# RCDudelTiny.net
KiCad netlist of a schematic drawn in EAGLE
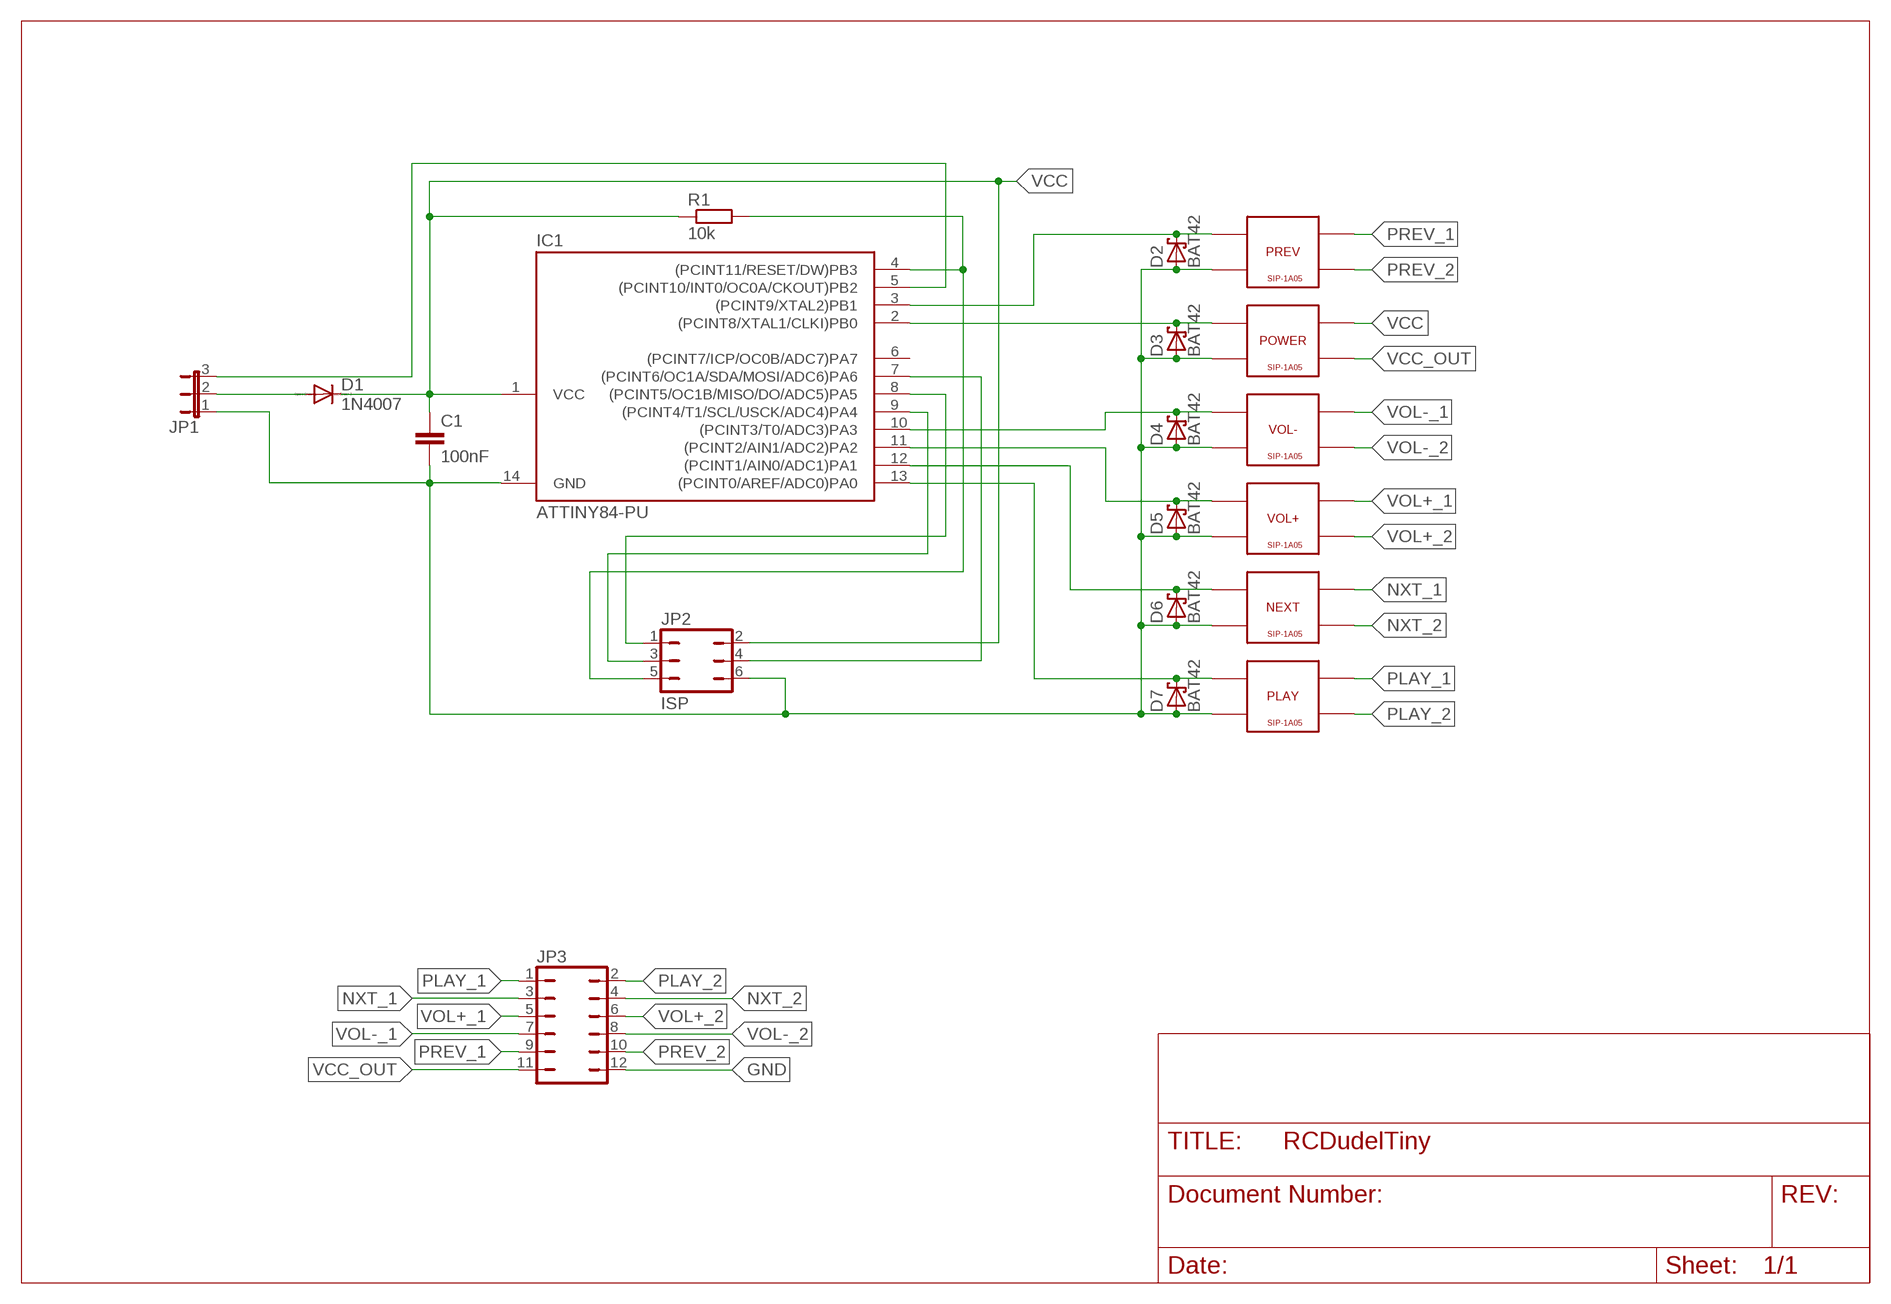
[diagram p0: schematic, sheet 1]

(export (version "E")
  (design (tool "Eeschema 10.0.6"))
  (components
    (comp (ref "C1")
      (value "100nF")
      (footprint "eagle-import:C025-025X050")
      (libsource (lib "eagle-import") (part "C-EU025-025X050"))
    )
    (comp (ref "D1")
      (value "1N4007")
      (footprint "eagle-import:DO41-10")
      (libsource (lib "eagle-import") (part "1N4004"))
    )
    (comp (ref "D2")
      (value "BAT42")
      (footprint "eagle-import:DO35-10")
      (libsource (lib "eagle-import") (part "BAT42"))
    )
    (comp (ref "D3")
      (value "BAT42")
      (footprint "eagle-import:DO35-10")
      (libsource (lib "eagle-import") (part "BAT42"))
    )
    (comp (ref "D4")
      (value "BAT42")
      (footprint "eagle-import:DO35-10")
      (libsource (lib "eagle-import") (part "BAT42"))
    )
    (comp (ref "D5")
      (value "BAT42")
      (footprint "eagle-import:DO35-10")
      (libsource (lib "eagle-import") (part "BAT42"))
    )
    (comp (ref "D6")
      (value "BAT42")
      (footprint "eagle-import:DO35-10")
      (libsource (lib "eagle-import") (part "BAT42"))
    )
    (comp (ref "D7")
      (value "BAT42")
      (footprint "eagle-import:DO35-10")
      (libsource (lib "eagle-import") (part "BAT42"))
    )
    (comp (ref "IC1")
      (value "ATTINY84-PU")
      (footprint "eagle-import:DIL14")
      (libsource (lib "eagle-import") (part "TINY24/44/84-PU"))
    )
    (comp (ref "JP1")
      (value "JP2EJP2_OHNE_TEXT")
      (footprint "eagle-import:JP2")
      (libsource (lib "eagle-import") (part "JP2EJP2_OHNE_TEXT"))
    )
    (comp (ref "JP2")
      (value "ISP")
      (footprint "eagle-import:JP3Q")
      (libsource (lib "eagle-import") (part "JP3Q"))
    )
    (comp (ref "JP3")
      (value "JP6Q")
      (footprint "eagle-import:JP6Q")
      (libsource (lib "eagle-import") (part "JP6Q"))
    )
    (comp (ref "NEXT")
      (value "SIP1A05")
      (footprint "eagle-import:SIP1A05")
      (libsource (lib "eagle-import") (part "SIP1A05"))
    )
    (comp (ref "PLAY")
      (value "SIP1A05")
      (footprint "eagle-import:SIP1A05")
      (libsource (lib "eagle-import") (part "SIP1A05"))
    )
    (comp (ref "POWER")
      (value "SIP1A05")
      (footprint "eagle-import:SIP1A05")
      (libsource (lib "eagle-import") (part "SIP1A05"))
    )
    (comp (ref "PREV")
      (value "SIP1A05")
      (footprint "eagle-import:SIP1A05")
      (libsource (lib "eagle-import") (part "SIP1A05"))
    )
    (comp (ref "R1")
      (value "10k")
      (footprint "eagle-import:0207_7")
      (libsource (lib "eagle-import") (part "R-EU_0207/7"))
    )
    (comp (ref "VOL+")
      (value "SIP1A05")
      (footprint "eagle-import:SIP1A05")
      (libsource (lib "eagle-import") (part "SIP1A05"))
    )
    (comp (ref "VOL-")
      (value "SIP1A05")
      (footprint "eagle-import:SIP1A05")
      (libsource (lib "eagle-import") (part "SIP1A05"))
    )
  )
  (nets
    (net (code "1") (name "GND") (class "Default")
      (node (ref "C1") (pin "2") (pinfunction "2_2") (pintype "passive"))
      (node (ref "D2") (pin "A") (pinfunction "A_A") (pintype "passive"))
      (node (ref "D3") (pin "A") (pinfunction "A_A") (pintype "passive"))
      (node (ref "D4") (pin "A") (pinfunction "A_A") (pintype "passive"))
      (node (ref "D5") (pin "A") (pinfunction "A_A") (pintype "passive"))
      (node (ref "D6") (pin "A") (pinfunction "A_A") (pintype "passive"))
      (node (ref "D7") (pin "A") (pinfunction "A_A") (pintype "passive"))
      (node (ref "IC1") (pin "14") (pinfunction "GND_14") (pintype "power_in"))
      (node (ref "JP1") (pin "1") (pinfunction "1_1") (pintype "passive"))
      (node (ref "JP2") (pin "6") (pinfunction "6_6") (pintype "passive"))
      (node (ref "JP3") (pin "12") (pinfunction "12_12") (pintype "passive"))
      (node (ref "NEXT") (pin "SP2") (pinfunction "SP2_SP2") (pintype "bidirectional"))
      (node (ref "PLAY") (pin "SP2") (pinfunction "SP2_SP2") (pintype "bidirectional"))
      (node (ref "POWER") (pin "SP2") (pinfunction "SP2_SP2") (pintype "bidirectional"))
      (node (ref "PREV") (pin "SP2") (pinfunction "SP2_SP2") (pintype "bidirectional"))
      (node (ref "VOL+") (pin "SP2") (pinfunction "SP2_SP2") (pintype "bidirectional"))
      (node (ref "VOL-") (pin "SP2") (pinfunction "SP2_SP2") (pintype "bidirectional"))
    )
    (net (code "2") (name "NXT_1") (class "Default")
      (node (ref "JP3") (pin "3") (pinfunction "3_3") (pintype "passive"))
      (node (ref "NEXT") (pin "K1") (pinfunction "K1_K1") (pintype "bidirectional"))
    )
    (net (code "3") (name "NXT_2") (class "Default")
      (node (ref "JP3") (pin "4") (pinfunction "4_4") (pintype "passive"))
      (node (ref "NEXT") (pin "K2") (pinfunction "K2_K2") (pintype "bidirectional"))
    )
    (net (code "4") (name "Net-(D1-PadA)") (class "Default")
      (node (ref "D1") (pin "A") (pinfunction "A_A") (pintype "passive"))
      (node (ref "JP1") (pin "2") (pinfunction "2_2") (pintype "passive"))
    )
    (net (code "5") (name "Net-(IC1-(PCINT0{slash}AREF{slash}ADC0)PA0)") (class "Default")
      (node (ref "D7") (pin "C") (pinfunction "C_C") (pintype "passive"))
      (node (ref "IC1") (pin "13") (pinfunction "(PCINT0/AREF/ADC0)PA0_13") (pintype "bidirectional"))
      (node (ref "PLAY") (pin "SP1") (pinfunction "SP1_SP1") (pintype "bidirectional"))
    )
    (net (code "6") (name "Net-(IC1-(PCINT1{slash}AIN0{slash}ADC1)PA1)") (class "Default")
      (node (ref "D6") (pin "C") (pinfunction "C_C") (pintype "passive"))
      (node (ref "IC1") (pin "12") (pinfunction "(PCINT1/AIN0/ADC1)PA1_12") (pintype "bidirectional"))
      (node (ref "NEXT") (pin "SP1") (pinfunction "SP1_SP1") (pintype "bidirectional"))
    )
    (net (code "7") (name "Net-(IC1-(PCINT2{slash}AIN1{slash}ADC2)PA2)") (class "Default")
      (node (ref "D5") (pin "C") (pinfunction "C_C") (pintype "passive"))
      (node (ref "IC1") (pin "11") (pinfunction "(PCINT2/AIN1/ADC2)PA2_11") (pintype "bidirectional"))
      (node (ref "VOL+") (pin "SP1") (pinfunction "SP1_SP1") (pintype "bidirectional"))
    )
    (net (code "8") (name "Net-(IC1-(PCINT3{slash}T0{slash}ADC3)PA3)") (class "Default")
      (node (ref "D4") (pin "C") (pinfunction "C_C") (pintype "passive"))
      (node (ref "IC1") (pin "10") (pinfunction "(PCINT3/T0/ADC3)PA3_10") (pintype "bidirectional"))
      (node (ref "VOL-") (pin "SP1") (pinfunction "SP1_SP1") (pintype "bidirectional"))
    )
    (net (code "9") (name "Net-(IC1-(PCINT4{slash}T1{slash}SCL{slash}USCK{slash}ADC4)PA4)") (class "Default")
      (node (ref "IC1") (pin "9") (pinfunction "(PCINT4/T1/SCL/USCK/ADC4)PA4_9") (pintype "bidirectional"))
      (node (ref "JP2") (pin "3") (pinfunction "3_3") (pintype "passive"))
    )
    (net (code "10") (name "Net-(IC1-(PCINT5{slash}OC1B{slash}MISO{slash}DO{slash}ADC5)PA5)") (class "Default")
      (node (ref "IC1") (pin "8") (pinfunction "(PCINT5/OC1B/MISO/DO/ADC5)PA5_8") (pintype "bidirectional"))
      (node (ref "JP2") (pin "1") (pinfunction "1_1") (pintype "passive"))
    )
    (net (code "11") (name "Net-(IC1-(PCINT6{slash}OC1A{slash}SDA{slash}MOSI{slash}ADC6)PA6)") (class "Default")
      (node (ref "IC1") (pin "7") (pinfunction "(PCINT6/OC1A/SDA/MOSI/ADC6)PA6_7") (pintype "bidirectional"))
      (node (ref "JP2") (pin "4") (pinfunction "4_4") (pintype "passive"))
    )
    (net (code "12") (name "Net-(IC1-(PCINT8{slash}XTAL1{slash}CLKI)PB0)") (class "Default")
      (node (ref "D3") (pin "C") (pinfunction "C_C") (pintype "passive"))
      (node (ref "IC1") (pin "2") (pinfunction "(PCINT8/XTAL1/CLKI)PB0_2") (pintype "bidirectional"))
      (node (ref "POWER") (pin "SP1") (pinfunction "SP1_SP1") (pintype "bidirectional"))
    )
    (net (code "13") (name "Net-(IC1-(PCINT9{slash}XTAL2)PB1)") (class "Default")
      (node (ref "D2") (pin "C") (pinfunction "C_C") (pintype "passive"))
      (node (ref "IC1") (pin "3") (pinfunction "(PCINT9/XTAL2)PB1_3") (pintype "bidirectional"))
      (node (ref "PREV") (pin "SP1") (pinfunction "SP1_SP1") (pintype "bidirectional"))
    )
    (net (code "14") (name "Net-(IC1-(PCINT10{slash}INT0{slash}OC0A{slash}CKOUT)PB2)") (class "Default")
      (node (ref "IC1") (pin "5") (pinfunction "(PCINT10/INT0/OC0A/CKOUT)PB2_5") (pintype "bidirectional"))
      (node (ref "JP1") (pin "3") (pinfunction "3_3") (pintype "passive"))
    )
    (net (code "15") (name "Net-(IC1-(PCINT11{slash}RESET{slash}DW)PB3)") (class "Default")
      (node (ref "IC1") (pin "4") (pinfunction "(PCINT11/RESET/DW)PB3_4") (pintype "bidirectional"))
      (node (ref "JP2") (pin "5") (pinfunction "5_5") (pintype "passive"))
      (node (ref "R1") (pin "2") (pinfunction "2_2") (pintype "passive"))
    )
    (net (code "16") (name "PLAY_1") (class "Default")
      (node (ref "JP3") (pin "1") (pinfunction "1_1") (pintype "passive"))
      (node (ref "PLAY") (pin "K1") (pinfunction "K1_K1") (pintype "bidirectional"))
    )
    (net (code "17") (name "PLAY_2") (class "Default")
      (node (ref "JP3") (pin "2") (pinfunction "2_2") (pintype "passive"))
      (node (ref "PLAY") (pin "K2") (pinfunction "K2_K2") (pintype "bidirectional"))
    )
    (net (code "18") (name "PREV_1") (class "Default")
      (node (ref "JP3") (pin "9") (pinfunction "9_9") (pintype "passive"))
      (node (ref "PREV") (pin "K1") (pinfunction "K1_K1") (pintype "bidirectional"))
    )
    (net (code "19") (name "PREV_2") (class "Default")
      (node (ref "JP3") (pin "10") (pinfunction "10_10") (pintype "passive"))
      (node (ref "PREV") (pin "K2") (pinfunction "K2_K2") (pintype "bidirectional"))
    )
    (net (code "20") (name "VCC") (class "Default")
      (node (ref "C1") (pin "1") (pinfunction "1_1") (pintype "passive"))
      (node (ref "D1") (pin "C") (pinfunction "C_C") (pintype "passive"))
      (node (ref "IC1") (pin "1") (pinfunction "VCC_1") (pintype "power_in"))
      (node (ref "JP2") (pin "2") (pinfunction "2_2") (pintype "passive"))
      (node (ref "POWER") (pin "K1") (pinfunction "K1_K1") (pintype "bidirectional"))
      (node (ref "R1") (pin "1") (pinfunction "1_1") (pintype "passive"))
    )
    (net (code "21") (name "VCC_OUT") (class "Default")
      (node (ref "JP3") (pin "11") (pinfunction "11_11") (pintype "passive"))
      (node (ref "POWER") (pin "K2") (pinfunction "K2_K2") (pintype "bidirectional"))
    )
    (net (code "22") (name "VOL+_1") (class "Default")
      (node (ref "JP3") (pin "5") (pinfunction "5_5") (pintype "passive"))
      (node (ref "VOL+") (pin "K1") (pinfunction "K1_K1") (pintype "bidirectional"))
    )
    (net (code "23") (name "VOL+_2") (class "Default")
      (node (ref "JP3") (pin "6") (pinfunction "6_6") (pintype "passive"))
      (node (ref "VOL+") (pin "K2") (pinfunction "K2_K2") (pintype "bidirectional"))
    )
    (net (code "24") (name "VOL-_1") (class "Default")
      (node (ref "JP3") (pin "7") (pinfunction "7_7") (pintype "passive"))
      (node (ref "VOL-") (pin "K1") (pinfunction "K1_K1") (pintype "bidirectional"))
    )
    (net (code "25") (name "VOL-_2") (class "Default")
      (node (ref "JP3") (pin "8") (pinfunction "8_8") (pintype "passive"))
      (node (ref "VOL-") (pin "K2") (pinfunction "K2_K2") (pintype "bidirectional"))
    )
    (net (code "26") (name "unconnected-(IC1-(PCINT7{slash}ICP{slash}OC0B{slash}ADC7)PA7-Pad6)") (class "Default")
      (node (ref "IC1") (pin "6") (pinfunction "(PCINT7/ICP/OC0B/ADC7)PA7_6") (pintype "bidirectional"))
    )
  )
)
